# SB_A005.net
KiCad netlist of a schematic drawn in EAGLE
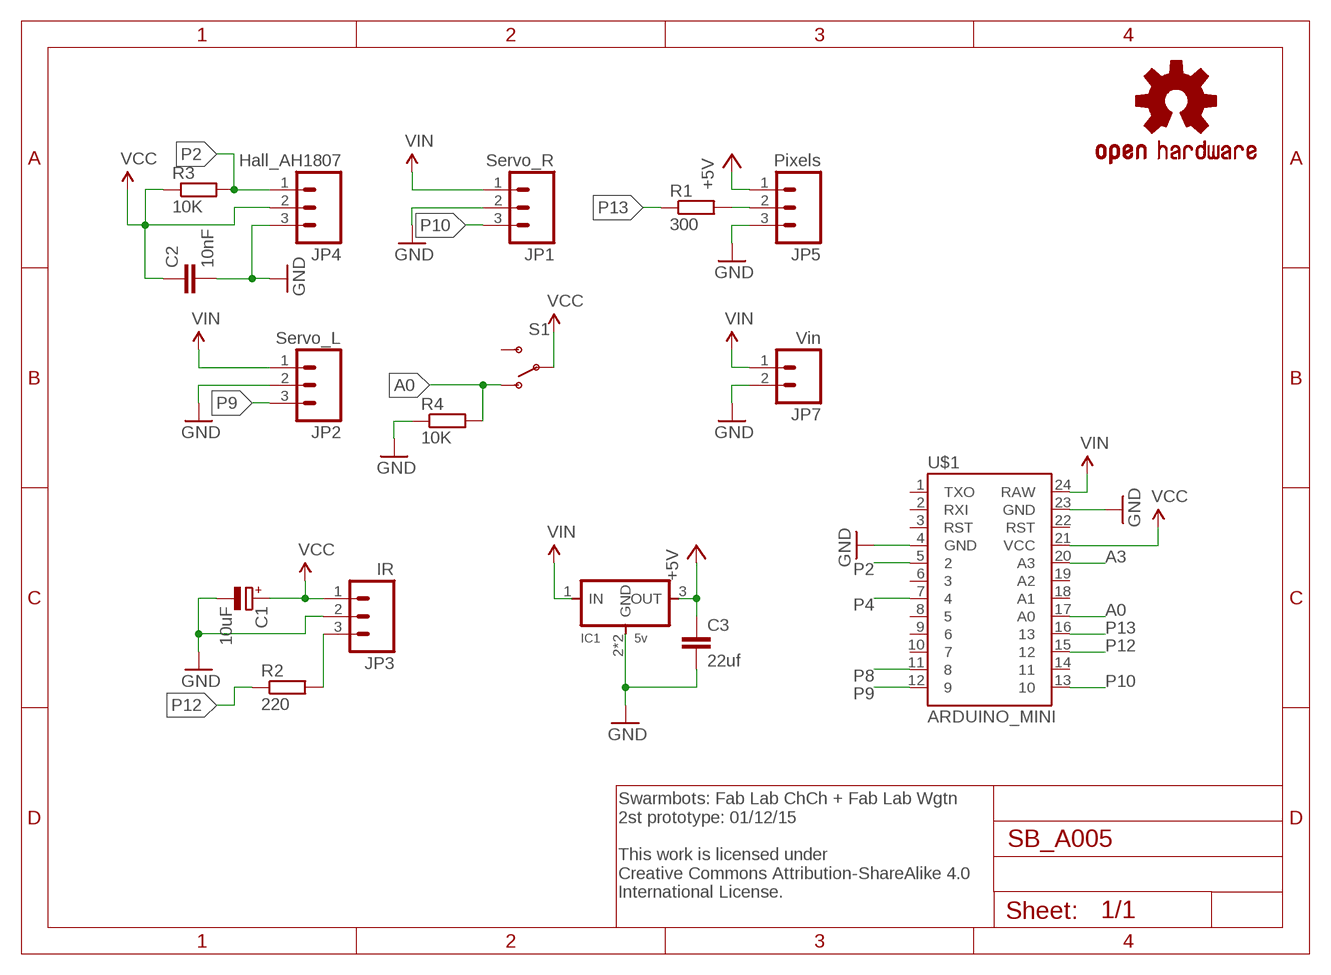
[diagram p0: schematic, sheet 1]

(export (version "E")
  (design (tool "Eeschema 10.0.6"))
  (components
    (comp (ref "C1")
      (value "10uF")
      (footprint "eagle-import:C_6032-28R")
      (libsource (lib "eagle-import") (part "CPOL-EUC/6032-28R"))
    )
    (comp (ref "C2")
      (value "10nF")
      (footprint "eagle-import:C1206")
      (libsource (lib "eagle-import") (part "C-EUC1206"))
    )
    (comp (ref "C3")
      (value "22uf")
      (footprint "eagle-import:C1206K")
      (libsource (lib "eagle-import") (part "C-EUC1206K"))
    )
    (comp (ref "IC1")
      (value "5v")
      (footprint "eagle-import:SOT223")
      (libsource (lib "eagle-import") (part "REGULATORSOT223"))
    )
    (comp (ref "JP1")
      (value "Servo_R")
      (footprint "eagle-import:1X03_LONGPADS")
      (libsource (lib "eagle-import") (part "M03LONGPADS"))
    )
    (comp (ref "JP2")
      (value "Servo_L")
      (footprint "eagle-import:1X03_LONGPADS")
      (libsource (lib "eagle-import") (part "M03LONGPADS"))
    )
    (comp (ref "JP3")
      (value "IR")
      (footprint "eagle-import:1X03_NO_SILK")
      (libsource (lib "eagle-import") (part "M031X03_NO_SILK"))
    )
    (comp (ref "JP4")
      (value "Hall_AH1807")
      (footprint "eagle-import:1X03_NO_SILK")
      (libsource (lib "eagle-import") (part "M031X03_NO_SILK"))
    )
    (comp (ref "JP5")
      (value "Pixels")
      (footprint "eagle-import:1X03_LONGPADS")
      (libsource (lib "eagle-import") (part "M03LONGPADS"))
    )
    (comp (ref "JP7")
      (value "Vin")
      (footprint "eagle-import:1X02_LONGPADS")
      (libsource (lib "eagle-import") (part "M02PTH3"))
    )
    (comp (ref "LOGO1")
      (value "OSHW-LOGOS")
      (footprint "eagle-import:OSHW-LOGO-S")
      (libsource (lib "eagle-import") (part "OSHW-LOGOS"))
    )
    (comp (ref "R1")
      (value "300")
      (footprint "eagle-import:M1206")
      (libsource (lib "eagle-import") (part "R-EU_M1206"))
    )
    (comp (ref "R2")
      (value "220")
      (footprint "eagle-import:M1206")
      (libsource (lib "eagle-import") (part "R-EU_M1206"))
    )
    (comp (ref "R3")
      (value "10K")
      (footprint "eagle-import:M1206")
      (libsource (lib "eagle-import") (part "R-EU_M1206"))
    )
    (comp (ref "R4")
      (value "10K")
      (footprint "eagle-import:M1206")
      (libsource (lib "eagle-import") (part "R-EU_M1206"))
    )
    (comp (ref "S1")
      (value "SWITCH-SPDTSMD2")
      (footprint "eagle-import:SWITCH-SPDT-SMD")
      (libsource (lib "eagle-import") (part "SWITCH-SPDTSMD2"))
    )
    (comp (ref "U$1")
      (value "ARDUINO_MINI")
      (footprint "eagle-import:ARDUINO_MINI")
      (libsource (lib "eagle-import") (part "ARDUINO_MINI"))
    )
  )
  (nets
    (net (code "1") (name "+5V") (class "Default")
      (node (ref "C3") (pin "1") (pinfunction "1_1") (pintype "passive"))
      (node (ref "IC1") (pin "3") (pinfunction "OUT_3") (pintype "bidirectional"))
      (node (ref "JP5") (pin "1") (pinfunction "1_1") (pintype "passive"))
    )
    (net (code "2") (name "/A3") (class "Default")
      (node (ref "U$1") (pin "20") (pinfunction "A3_20") (pintype "bidirectional"))
    )
    (net (code "3") (name "/P4") (class "Default")
      (node (ref "U$1") (pin "7") (pinfunction "4_7") (pintype "bidirectional"))
    )
    (net (code "4") (name "/P8") (class "Default")
      (node (ref "U$1") (pin "11") (pinfunction "8_11") (pintype "bidirectional"))
    )
    (net (code "5") (name "A0") (class "Default")
      (node (ref "R4") (pin "2") (pinfunction "2_2") (pintype "passive"))
      (node (ref "S1") (pin "1") (pinfunction "O_1") (pintype "passive"))
      (node (ref "U$1") (pin "17") (pinfunction "A0_17") (pintype "bidirectional"))
    )
    (net (code "6") (name "GND") (class "Default")
      (node (ref "C1") (pin "-") (pinfunction "-_-") (pintype "passive"))
      (node (ref "C2") (pin "2") (pinfunction "2_2") (pintype "passive"))
      (node (ref "C3") (pin "2") (pinfunction "2_2") (pintype "passive"))
      (node (ref "IC1") (pin "2") (pinfunction "GND_2") (pintype "bidirectional"))
      (node (ref "IC1") (pin "4") (pinfunction "GND_4") (pintype "bidirectional"))
      (node (ref "JP1") (pin "2") (pinfunction "2_2") (pintype "passive"))
      (node (ref "JP2") (pin "2") (pinfunction "2_2") (pintype "passive"))
      (node (ref "JP3") (pin "2") (pinfunction "2_2") (pintype "passive"))
      (node (ref "JP4") (pin "3") (pinfunction "3_3") (pintype "passive"))
      (node (ref "JP5") (pin "3") (pinfunction "3_3") (pintype "passive"))
      (node (ref "JP7") (pin "2") (pinfunction "2_2") (pintype "passive"))
      (node (ref "R4") (pin "1") (pinfunction "1_1") (pintype "passive"))
      (node (ref "U$1") (pin "23") (pinfunction "GND_23") (pintype "bidirectional"))
      (node (ref "U$1") (pin "4") (pinfunction "GND_4") (pintype "bidirectional"))
    )
    (net (code "7") (name "Net-(JP3-Pad3)") (class "Default")
      (node (ref "JP3") (pin "3") (pinfunction "3_3") (pintype "passive"))
      (node (ref "R2") (pin "2") (pinfunction "2_2") (pintype "passive"))
    )
    (net (code "8") (name "Net-(JP5-Pad2)") (class "Default")
      (node (ref "JP5") (pin "2") (pinfunction "2_2") (pintype "passive"))
      (node (ref "R1") (pin "2") (pinfunction "2_2") (pintype "passive"))
    )
    (net (code "9") (name "P2") (class "Default")
      (node (ref "JP4") (pin "1") (pinfunction "1_1") (pintype "passive"))
      (node (ref "R3") (pin "2") (pinfunction "2_2") (pintype "passive"))
      (node (ref "U$1") (pin "5") (pinfunction "2_5") (pintype "bidirectional"))
    )
    (net (code "10") (name "P9") (class "Default")
      (node (ref "JP2") (pin "3") (pinfunction "3_3") (pintype "passive"))
      (node (ref "U$1") (pin "12") (pinfunction "9_12") (pintype "bidirectional"))
    )
    (net (code "11") (name "P10") (class "Default")
      (node (ref "JP1") (pin "3") (pinfunction "3_3") (pintype "passive"))
      (node (ref "U$1") (pin "13") (pinfunction "10_13") (pintype "bidirectional"))
    )
    (net (code "12") (name "P12") (class "Default")
      (node (ref "R2") (pin "1") (pinfunction "1_1") (pintype "passive"))
      (node (ref "U$1") (pin "15") (pinfunction "12_15") (pintype "bidirectional"))
    )
    (net (code "13") (name "P13") (class "Default")
      (node (ref "R1") (pin "1") (pinfunction "1_1") (pintype "passive"))
      (node (ref "U$1") (pin "16") (pinfunction "13_16") (pintype "bidirectional"))
    )
    (net (code "14") (name "VCC") (class "Default")
      (node (ref "C1") (pin "+") (pinfunction "+_+") (pintype "passive"))
      (node (ref "C2") (pin "1") (pinfunction "1_1") (pintype "passive"))
      (node (ref "JP3") (pin "1") (pinfunction "1_1") (pintype "passive"))
      (node (ref "JP4") (pin "2") (pinfunction "2_2") (pintype "passive"))
      (node (ref "R3") (pin "1") (pinfunction "1_1") (pintype "passive"))
      (node (ref "S1") (pin "2") (pinfunction "P_2") (pintype "passive"))
      (node (ref "U$1") (pin "21") (pinfunction "VCC_21") (pintype "bidirectional"))
    )
    (net (code "15") (name "VIN") (class "Default")
      (node (ref "IC1") (pin "1") (pinfunction "IN_1") (pintype "bidirectional"))
      (node (ref "JP1") (pin "1") (pinfunction "1_1") (pintype "passive"))
      (node (ref "JP2") (pin "1") (pinfunction "1_1") (pintype "passive"))
      (node (ref "JP7") (pin "1") (pinfunction "1_1") (pintype "passive"))
      (node (ref "U$1") (pin "24") (pinfunction "RAW_24") (pintype "bidirectional"))
    )
    (net (code "16") (name "unconnected-(S1-S-Pad3)") (class "Default")
      (node (ref "S1") (pin "3") (pinfunction "S_3") (pintype "passive"))
    )
    (net (code "17") (name "unconnected-(U$1-3-Pad6)") (class "Default")
      (node (ref "U$1") (pin "6") (pinfunction "3_6") (pintype "bidirectional"))
    )
    (net (code "18") (name "unconnected-(U$1-5-Pad8)") (class "Default")
      (node (ref "U$1") (pin "8") (pinfunction "5_8") (pintype "bidirectional"))
    )
    (net (code "19") (name "unconnected-(U$1-6-Pad9)") (class "Default")
      (node (ref "U$1") (pin "9") (pinfunction "6_9") (pintype "bidirectional"))
    )
    (net (code "20") (name "unconnected-(U$1-7-Pad10)") (class "Default")
      (node (ref "U$1") (pin "10") (pinfunction "7_10") (pintype "bidirectional"))
    )
    (net (code "21") (name "unconnected-(U$1-11-Pad14)") (class "Default")
      (node (ref "U$1") (pin "14") (pinfunction "11_14") (pintype "bidirectional"))
    )
    (net (code "22") (name "unconnected-(U$1-A1-Pad18)") (class "Default")
      (node (ref "U$1") (pin "18") (pinfunction "A1_18") (pintype "bidirectional"))
    )
    (net (code "23") (name "unconnected-(U$1-A2-Pad19)") (class "Default")
      (node (ref "U$1") (pin "19") (pinfunction "A2_19") (pintype "bidirectional"))
    )
    (net (code "24") (name "unconnected-(U$1-RST-Pad3)") (class "Default")
      (node (ref "U$1") (pin "3") (pinfunction "RST_3") (pintype "bidirectional"))
    )
    (net (code "25") (name "unconnected-(U$1-RST-Pad22)") (class "Default")
      (node (ref "U$1") (pin "22") (pinfunction "RST_22") (pintype "bidirectional"))
    )
    (net (code "26") (name "unconnected-(U$1-RXI-Pad2)") (class "Default")
      (node (ref "U$1") (pin "2") (pinfunction "RXI_2") (pintype "bidirectional"))
    )
    (net (code "27") (name "unconnected-(U$1-TXO-Pad1)") (class "Default")
      (node (ref "U$1") (pin "1") (pinfunction "TXO_1") (pintype "bidirectional"))
    )
  )
)
